# Connectors.net
KiCad netlist of a schematic drawn in Altium Designer
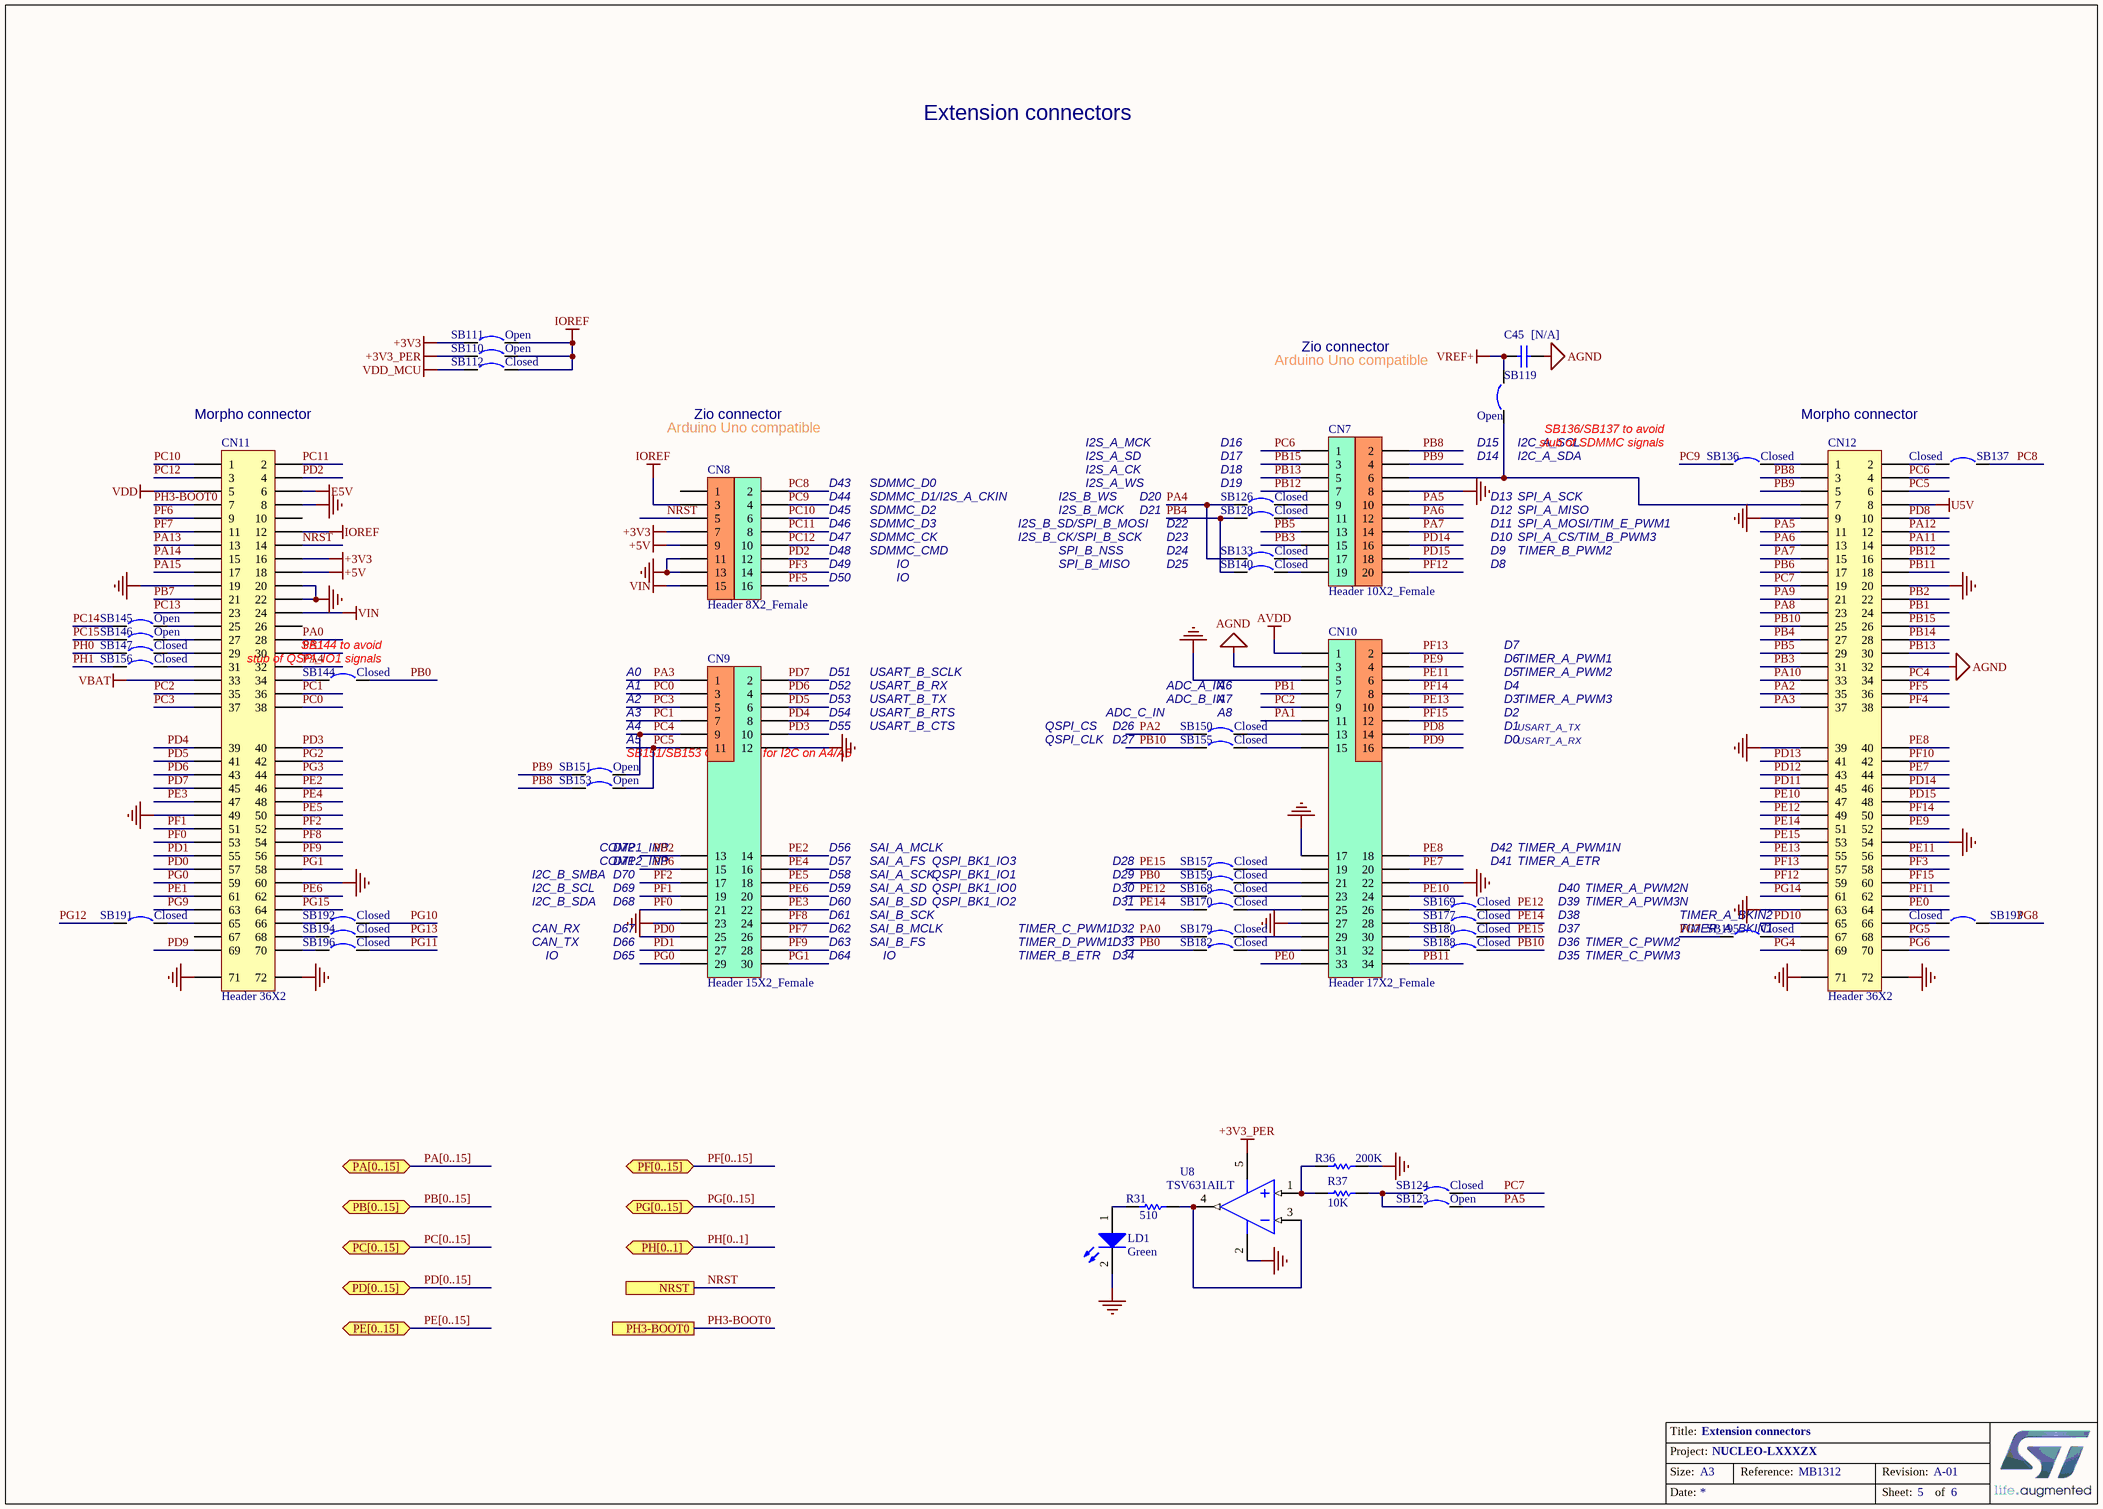
[diagram p0: Connectors.SchDoc]

(export (version "E")
  (design (tool "Eeschema 10.0.6"))
  (components
    (comp (ref "C45")
      (value "[N/A]")
      (footprint "0603C")
      (description "Capacitor,100nF,10%,16V,X7R,0603,YAGEO")
      (fields (field (name "PUBLISHER") "Altium Limited"))
      (libsource (lib "Miscellaneous Devices") (part "Cap"))
    )
    (comp (ref "CN7")
      (value "Header 10X2_Female")
      (footprint "HDR_10x2_2R54_V_F")
      (description "Header, 10-Pin, Dual row,female")
      (fields (field (name "PUBLISHER") "Altium Limited"))
      (libsource (lib "MB1137") (part "Header 10X2_Female"))
    )
    (comp (ref "CN8")
      (value "Header 8X2_Female")
      (footprint "HDR_8x2_2R54_V_F")
      (description "Header, 8-Pin, Dual row,female")
      (fields (field (name "PUBLISHER") "Altium Limited"))
      (libsource (lib "MB1137") (part "Header 8X2_Female"))
    )
    (comp (ref "CN9")
      (value "Header 15X2_Female")
      (footprint "HDR_15x2_2R54_V_F")
      (description "Header, 15-Pin, Dual row,female")
      (fields (field (name "PUBLISHER") "Altium Limited"))
      (libsource (lib "MB1137") (part "Header 15X2_Female"))
    )
    (comp (ref "CN10")
      (value "Header 17X2_Female")
      (footprint "HDR_17x2_2R54_V_F")
      (description "Header, 17-Pin, Dual row,female")
      (fields (field (name "PUBLISHER") "Altium Limited"))
      (libsource (lib "MB1137") (part "Header 17X2_Female"))
    )
    (comp (ref "CN11")
      (value "Header 36X2")
      (footprint "HDR_2x36_2R54_V_M")
      (description "Header, 36-Pin, Dual row")
      (fields (field (name "PUBLISHER") "Altium Limited"))
      (libsource (lib "MB1137") (part "Header 36X2"))
    )
    (comp (ref "CN12")
      (value "Header 36X2")
      (footprint "HDR_2x36_2R54_V_M")
      (description "Header, 36-Pin, Dual row")
      (fields (field (name "PUBLISHER") "Altium Limited"))
      (libsource (lib "MB1137") (part "Header 36X2"))
    )
    (comp (ref "LD1")
      (value "Green")
      (footprint "0603D-G")
      (description "Typical RED, GREEN, YELLOW, AMBER GaAs LED")
      (fields (field (name "PUBLISHER") "Altium Limited"))
      (libsource (lib "Miscellaneous Devices") (part "LED2"))
    )
    (comp (ref "R31")
      (value "510")
      (footprint "0603R")
      (description "Resistor")
      (fields (field (name "PUBLISHER") "Altium Limited"))
      (libsource (lib "Miscellaneous Devices") (part "Res1"))
    )
    (comp (ref "R36")
      (value "200K")
      (footprint "0603R")
      (description "Resistor")
      (fields (field (name "PUBLISHER") "Altium Limited"))
      (libsource (lib "Miscellaneous Devices") (part "res1"))
    )
    (comp (ref "R37")
      (value "10K")
      (footprint "0603R")
      (description "Resistor")
      (fields (field (name "PUBLISHER") "Altium Limited"))
      (libsource (lib "Miscellaneous Devices") (part "res1"))
    )
    (comp (ref "SB110")
      (value "Open")
      (footprint "SB_0603")
      (description "Circuit Breaker")
      (fields (field (name "PUBLISHER") "Altium Limited"))
      (libsource (lib "MB1167") (part "Circuit Breaker"))
    )
    (comp (ref "SB111")
      (value "Open")
      (footprint "SB_0603")
      (description "Circuit Breaker")
      (fields (field (name "PUBLISHER") "Altium Limited"))
      (libsource (lib "MB1167") (part "Circuit Breaker"))
    )
    (comp (ref "SB112")
      (value "Closed")
      (footprint "SB_0603")
      (description "Circuit Breaker")
      (fields (field (name "PUBLISHER") "Altium Limited"))
      (libsource (lib "MB1167") (part "Circuit Breaker_close"))
    )
    (comp (ref "SB119")
      (value "Open")
      (footprint "SB_0603")
      (description "Circuit Breaker")
      (fields (field (name "PUBLISHER") "Altium Limited"))
      (libsource (lib "") (part "Circuit Breaker_2"))
    )
    (comp (ref "SB123")
      (value "Open")
      (footprint "SB_0603")
      (description "Circuit Breaker")
      (fields (field (name "PUBLISHER") "Altium Limited"))
      (libsource (lib "MB1167") (part "Circuit Breaker"))
    )
    (comp (ref "SB124")
      (value "Closed")
      (footprint "SB_0603")
      (description "Circuit Breaker")
      (fields (field (name "PUBLISHER") "Altium Limited"))
      (libsource (lib "") (part "Circuit Breaker_close_1"))
    )
    (comp (ref "SB126")
      (value "Closed")
      (footprint "SB_0603")
      (description "Circuit Breaker")
      (fields (field (name "PUBLISHER") "Altium Limited"))
      (libsource (lib "MB1167") (part "Circuit Breaker_close"))
    )
    (comp (ref "SB128")
      (value "Closed")
      (footprint "SB_0603")
      (description "Circuit Breaker")
      (fields (field (name "PUBLISHER") "Altium Limited"))
      (libsource (lib "MB1167") (part "Circuit Breaker_close"))
    )
    (comp (ref "SB133")
      (value "Closed")
      (footprint "SB_0603")
      (description "Circuit Breaker")
      (fields (field (name "PUBLISHER") "Altium Limited"))
      (libsource (lib "MB1167") (part "Circuit Breaker_close"))
    )
    (comp (ref "SB136")
      (value "Closed")
      (footprint "SB_0603")
      (description "Circuit Breaker")
      (fields (field (name "PUBLISHER") "Altium Limited"))
      (libsource (lib "MB1167") (part "Circuit Breaker_close"))
    )
    (comp (ref "SB137")
      (value "Closed")
      (footprint "SB_0603")
      (description "Circuit Breaker")
      (fields (field (name "PUBLISHER") "Altium Limited"))
      (libsource (lib "") (part "Circuit Breaker_close_1"))
    )
    (comp (ref "SB140")
      (value "Closed")
      (footprint "SB_0603")
      (description "Circuit Breaker")
      (fields (field (name "PUBLISHER") "Altium Limited"))
      (libsource (lib "MB1167") (part "Circuit Breaker_close"))
    )
    (comp (ref "SB144")
      (value "Closed")
      (footprint "SB_0603")
      (description "Circuit Breaker")
      (fields (field (name "PUBLISHER") "Altium Limited"))
      (libsource (lib "MB1167") (part "Circuit Breaker_close"))
    )
    (comp (ref "SB145")
      (value "Open")
      (footprint "SB_0603")
      (description "Circuit Breaker")
      (fields (field (name "PUBLISHER") "Altium Limited"))
      (libsource (lib "MB1167") (part "Circuit Breaker"))
    )
    (comp (ref "SB146")
      (value "Open")
      (footprint "SB_0603")
      (description "Circuit Breaker")
      (fields (field (name "PUBLISHER") "Altium Limited"))
      (libsource (lib "MB1167") (part "Circuit Breaker"))
    )
    (comp (ref "SB147")
      (value "Closed")
      (footprint "SB_0603")
      (description "Circuit Breaker")
      (fields (field (name "PUBLISHER") "Altium Limited"))
      (libsource (lib "MB1167") (part "Circuit Breaker_close"))
    )
    (comp (ref "SB150")
      (value "Closed")
      (footprint "SB_0603")
      (description "Circuit Breaker")
      (fields (field (name "PUBLISHER") "Altium Limited"))
      (libsource (lib "MB1167") (part "Circuit Breaker_close"))
    )
    (comp (ref "SB151")
      (value "Open")
      (footprint "SB_0603")
      (description "Circuit Breaker")
      (fields (field (name "PUBLISHER") "Altium Limited"))
      (libsource (lib "") (part "Circuit Breaker_1"))
    )
    (comp (ref "SB153")
      (value "Open")
      (footprint "SB_0603")
      (description "Circuit Breaker")
      (fields (field (name "PUBLISHER") "Altium Limited"))
      (libsource (lib "") (part "Circuit Breaker_1"))
    )
    (comp (ref "SB155")
      (value "Closed")
      (footprint "SB_0603")
      (description "Circuit Breaker")
      (fields (field (name "PUBLISHER") "Altium Limited"))
      (libsource (lib "MB1167") (part "Circuit Breaker_close"))
    )
    (comp (ref "SB156")
      (value "Closed")
      (footprint "SB_0603")
      (description "Circuit Breaker")
      (fields (field (name "PUBLISHER") "Altium Limited"))
      (libsource (lib "MB1167") (part "Circuit Breaker_close"))
    )
    (comp (ref "SB157")
      (value "Closed")
      (footprint "SB_0603")
      (description "Circuit Breaker")
      (fields (field (name "PUBLISHER") "Altium Limited"))
      (libsource (lib "MB1167") (part "Circuit Breaker_close"))
    )
    (comp (ref "SB159")
      (value "Closed")
      (footprint "SB_0603")
      (description "Circuit Breaker")
      (fields (field (name "PUBLISHER") "Altium Limited"))
      (libsource (lib "MB1167") (part "Circuit Breaker_close"))
    )
    (comp (ref "SB168")
      (value "Closed")
      (footprint "SB_0603")
      (description "Circuit Breaker")
      (fields (field (name "PUBLISHER") "Altium Limited"))
      (libsource (lib "MB1167") (part "Circuit Breaker_close"))
    )
    (comp (ref "SB169")
      (value "Closed")
      (footprint "SB_0603")
      (description "Circuit Breaker")
      (fields (field (name "PUBLISHER") "Altium Limited"))
      (libsource (lib "MB1167") (part "Circuit Breaker_close"))
    )
    (comp (ref "SB170")
      (value "Closed")
      (footprint "SB_0603")
      (description "Circuit Breaker")
      (fields (field (name "PUBLISHER") "Altium Limited"))
      (libsource (lib "MB1167") (part "Circuit Breaker_close"))
    )
    (comp (ref "SB177")
      (value "Closed")
      (footprint "SB_0603")
      (description "Circuit Breaker")
      (fields (field (name "PUBLISHER") "Altium Limited"))
      (libsource (lib "MB1167") (part "Circuit Breaker_close"))
    )
    (comp (ref "SB179")
      (value "Closed")
      (footprint "SB_0603")
      (description "Circuit Breaker")
      (fields (field (name "PUBLISHER") "Altium Limited"))
      (libsource (lib "MB1167") (part "Circuit Breaker_close"))
    )
    (comp (ref "SB180")
      (value "Closed")
      (footprint "SB_0603")
      (description "Circuit Breaker")
      (fields (field (name "PUBLISHER") "Altium Limited"))
      (libsource (lib "MB1167") (part "Circuit Breaker_close"))
    )
    (comp (ref "SB182")
      (value "Closed")
      (footprint "SB_0603")
      (description "Circuit Breaker")
      (fields (field (name "PUBLISHER") "Altium Limited"))
      (libsource (lib "MB1167") (part "Circuit Breaker_close"))
    )
    (comp (ref "SB188")
      (value "Closed")
      (footprint "SB_0603")
      (description "Circuit Breaker")
      (fields (field (name "PUBLISHER") "Altium Limited"))
      (libsource (lib "MB1167") (part "Circuit Breaker_close"))
    )
    (comp (ref "SB191")
      (value "Closed")
      (footprint "SB_0603")
      (description "Circuit Breaker")
      (fields (field (name "PUBLISHER") "Altium Limited"))
      (libsource (lib "MB1167") (part "Circuit Breaker_close"))
    )
    (comp (ref "SB192")
      (value "Closed")
      (footprint "SB_0603")
      (description "Circuit Breaker")
      (fields (field (name "PUBLISHER") "Altium Limited"))
      (libsource (lib "MB1167") (part "Circuit Breaker_close"))
    )
    (comp (ref "SB193")
      (value "Closed")
      (footprint "SB_0603")
      (description "Circuit Breaker")
      (fields (field (name "PUBLISHER") "Altium Limited"))
      (libsource (lib "MB1167") (part "Circuit Breaker_close"))
    )
    (comp (ref "SB194")
      (value "Closed")
      (footprint "SB_0603")
      (description "Circuit Breaker")
      (fields (field (name "PUBLISHER") "Altium Limited"))
      (libsource (lib "MB1167") (part "Circuit Breaker_close"))
    )
    (comp (ref "SB195")
      (value "Closed")
      (footprint "SB_0603")
      (description "Circuit Breaker")
      (fields (field (name "PUBLISHER") "Altium Limited"))
      (libsource (lib "MB1167") (part "Circuit Breaker_close"))
    )
    (comp (ref "SB196")
      (value "Closed")
      (footprint "SB_0603")
      (description "Circuit Breaker")
      (fields (field (name "PUBLISHER") "Altium Limited"))
      (libsource (lib "MB1167") (part "Circuit Breaker_close"))
    )
    (comp (ref "U8")
      (value "TSV631AILT")
      (footprint "SOT-23-5L")
      (libsource (lib "MB988") (part "TSV631AILT"))
    )
  )
  (nets
    (net (code "1") (name "+3V3") (class "Default")
      (node (ref "CN11") (pin "16") (pinfunction "16_16") (pintype "passive"))
      (node (ref "CN8") (pin "7") (pinfunction "7_7") (pintype "passive"))
      (node (ref "SB111") (pin "1") (pinfunction "1_1") (pintype "passive"))
    )
    (net (code "2") (name "+3V3_PER") (class "Default")
      (node (ref "SB110") (pin "1") (pinfunction "1_1") (pintype "passive"))
      (node (ref "U8") (pin "5") (pinfunction "VCC_5") (pintype "power_in"))
    )
    (net (code "3") (name "+5V") (class "Default")
      (node (ref "CN11") (pin "18") (pinfunction "18_18") (pintype "passive"))
      (node (ref "CN8") (pin "9") (pinfunction "9_9") (pintype "passive"))
    )
    (net (code "4") (name "/NRST") (class "Default")
      (node (ref "CN11") (pin "14") (pinfunction "14_14") (pintype "passive"))
      (node (ref "CN8") (pin "5") (pinfunction "5_5") (pintype "passive"))
    )
    (net (code "5") (name "/PA0") (class "Default")
      (node (ref "CN11") (pin "28") (pinfunction "28_28") (pintype "passive"))
      (node (ref "SB179") (pin "1") (pinfunction "1_1") (pintype "passive"))
    )
    (net (code "6") (name "/PA1") (class "Default")
      (node (ref "CN10") (pin "11") (pinfunction "11_11") (pintype "passive"))
      (node (ref "CN11") (pin "30") (pinfunction "30_30") (pintype "passive"))
    )
    (net (code "7") (name "/PA2") (class "Default")
      (node (ref "CN12") (pin "35") (pinfunction "35_35") (pintype "passive"))
      (node (ref "SB150") (pin "1") (pinfunction "1_1") (pintype "passive"))
    )
    (net (code "8") (name "/PA3") (class "Default")
      (node (ref "CN12") (pin "37") (pinfunction "37_37") (pintype "passive"))
      (node (ref "CN9") (pin "1") (pinfunction "1_1") (pintype "passive"))
    )
    (net (code "9") (name "/PA4") (class "Default")
      (node (ref "CN11") (pin "32") (pinfunction "32_32") (pintype "passive"))
      (node (ref "SB126") (pin "1") (pinfunction "1_1") (pintype "passive"))
      (node (ref "SB133") (pin "1") (pinfunction "1_1") (pintype "passive"))
    )
    (net (code "10") (name "/PA5") (class "Default")
      (node (ref "CN12") (pin "11") (pinfunction "11_11") (pintype "passive"))
      (node (ref "CN7") (pin "10") (pinfunction "10_10") (pintype "passive"))
      (node (ref "SB123") (pin "2") (pinfunction "2_2") (pintype "passive"))
    )
    (net (code "11") (name "/PA6") (class "Default")
      (node (ref "CN12") (pin "13") (pinfunction "13_13") (pintype "passive"))
      (node (ref "CN7") (pin "12") (pinfunction "12_12") (pintype "passive"))
    )
    (net (code "12") (name "/PA7") (class "Default")
      (node (ref "CN12") (pin "15") (pinfunction "15_15") (pintype "passive"))
      (node (ref "CN7") (pin "14") (pinfunction "14_14") (pintype "passive"))
    )
    (net (code "13") (name "/PA8") (class "Default")
      (node (ref "CN12") (pin "23") (pinfunction "23_23") (pintype "passive"))
    )
    (net (code "14") (name "/PA9") (class "Default")
      (node (ref "CN12") (pin "21") (pinfunction "21_21") (pintype "passive"))
    )
    (net (code "15") (name "/PA10") (class "Default")
      (node (ref "CN12") (pin "33") (pinfunction "33_33") (pintype "passive"))
    )
    (net (code "16") (name "/PA11") (class "Default")
      (node (ref "CN12") (pin "14") (pinfunction "14_14") (pintype "passive"))
    )
    (net (code "17") (name "/PA12") (class "Default")
      (node (ref "CN12") (pin "12") (pinfunction "12_12") (pintype "passive"))
    )
    (net (code "18") (name "/PA13") (class "Default")
      (node (ref "CN11") (pin "13") (pinfunction "13_13") (pintype "passive"))
    )
    (net (code "19") (name "/PA14") (class "Default")
      (node (ref "CN11") (pin "15") (pinfunction "15_15") (pintype "passive"))
    )
    (net (code "20") (name "/PA15") (class "Default")
      (node (ref "CN11") (pin "17") (pinfunction "17_17") (pintype "passive"))
    )
    (net (code "22") (name "/PB0") (class "Default")
      (node (ref "SB144") (pin "2") (pinfunction "2_2") (pintype "passive"))
      (node (ref "SB159") (pin "1") (pinfunction "1_1") (pintype "passive"))
      (node (ref "SB182") (pin "1") (pinfunction "1_1") (pintype "passive"))
    )
    (net (code "23") (name "/PB1") (class "Default")
      (node (ref "CN10") (pin "7") (pinfunction "7_7") (pintype "passive"))
      (node (ref "CN12") (pin "24") (pinfunction "24_24") (pintype "passive"))
    )
    (net (code "24") (name "/PB2") (class "Default")
      (node (ref "CN12") (pin "22") (pinfunction "22_22") (pintype "passive"))
      (node (ref "CN9") (pin "13") (pinfunction "13_13") (pintype "passive"))
    )
    (net (code "25") (name "/PB3") (class "Default")
      (node (ref "CN12") (pin "31") (pinfunction "31_31") (pintype "passive"))
      (node (ref "CN7") (pin "15") (pinfunction "15_15") (pintype "passive"))
    )
    (net (code "26") (name "/PB4") (class "Default")
      (node (ref "CN12") (pin "27") (pinfunction "27_27") (pintype "passive"))
      (node (ref "SB128") (pin "1") (pinfunction "1_1") (pintype "passive"))
      (node (ref "SB140") (pin "1") (pinfunction "1_1") (pintype "passive"))
    )
    (net (code "27") (name "/PB5") (class "Default")
      (node (ref "CN12") (pin "29") (pinfunction "29_29") (pintype "passive"))
      (node (ref "CN7") (pin "13") (pinfunction "13_13") (pintype "passive"))
    )
    (net (code "28") (name "/PB6") (class "Default")
      (node (ref "CN12") (pin "17") (pinfunction "17_17") (pintype "passive"))
      (node (ref "CN9") (pin "15") (pinfunction "15_15") (pintype "passive"))
    )
    (net (code "29") (name "/PB7") (class "Default")
      (node (ref "CN11") (pin "21") (pinfunction "21_21") (pintype "passive"))
    )
    (net (code "30") (name "/PB8") (class "Default")
      (node (ref "CN12") (pin "3") (pinfunction "3_3") (pintype "passive"))
      (node (ref "CN7") (pin "2") (pinfunction "2_2") (pintype "passive"))
      (node (ref "SB153") (pin "2") (pinfunction "2_2") (pintype "passive"))
    )
    (net (code "31") (name "/PB9") (class "Default")
      (node (ref "CN12") (pin "5") (pinfunction "5_5") (pintype "passive"))
      (node (ref "CN7") (pin "4") (pinfunction "4_4") (pintype "passive"))
      (node (ref "SB151") (pin "2") (pinfunction "2_2") (pintype "passive"))
    )
    (net (code "32") (name "/PB10") (class "Default")
      (node (ref "CN12") (pin "25") (pinfunction "25_25") (pintype "passive"))
      (node (ref "SB155") (pin "1") (pinfunction "1_1") (pintype "passive"))
      (node (ref "SB188") (pin "2") (pinfunction "2_2") (pintype "passive"))
    )
    (net (code "33") (name "/PB11") (class "Default")
      (node (ref "CN10") (pin "34") (pinfunction "34_34") (pintype "passive"))
      (node (ref "CN12") (pin "18") (pinfunction "18_18") (pintype "passive"))
    )
    (net (code "34") (name "/PB12") (class "Default")
      (node (ref "CN12") (pin "16") (pinfunction "16_16") (pintype "passive"))
      (node (ref "CN7") (pin "7") (pinfunction "7_7") (pintype "passive"))
    )
    (net (code "35") (name "/PB13") (class "Default")
      (node (ref "CN12") (pin "30") (pinfunction "30_30") (pintype "passive"))
      (node (ref "CN7") (pin "5") (pinfunction "5_5") (pintype "passive"))
    )
    (net (code "36") (name "/PB14") (class "Default")
      (node (ref "CN12") (pin "28") (pinfunction "28_28") (pintype "passive"))
    )
    (net (code "37") (name "/PB15") (class "Default")
      (node (ref "CN12") (pin "26") (pinfunction "26_26") (pintype "passive"))
      (node (ref "CN7") (pin "3") (pinfunction "3_3") (pintype "passive"))
    )
    (net (code "39") (name "/PC0") (class "Default")
      (node (ref "CN11") (pin "38") (pinfunction "38_38") (pintype "passive"))
      (node (ref "CN9") (pin "3") (pinfunction "3_3") (pintype "passive"))
    )
    (net (code "40") (name "/PC1") (class "Default")
      (node (ref "CN11") (pin "36") (pinfunction "36_36") (pintype "passive"))
      (node (ref "CN9") (pin "7") (pinfunction "7_7") (pintype "passive"))
    )
    (net (code "41") (name "/PC2") (class "Default")
      (node (ref "CN10") (pin "9") (pinfunction "9_9") (pintype "passive"))
      (node (ref "CN11") (pin "35") (pinfunction "35_35") (pintype "passive"))
    )
    (net (code "42") (name "/PC3") (class "Default")
      (node (ref "CN11") (pin "37") (pinfunction "37_37") (pintype "passive"))
      (node (ref "CN9") (pin "5") (pinfunction "5_5") (pintype "passive"))
    )
    (net (code "43") (name "/PC4") (class "Default")
      (node (ref "CN12") (pin "34") (pinfunction "34_34") (pintype "passive"))
      (node (ref "CN9") (pin "9") (pinfunction "9_9") (pintype "passive"))
      (node (ref "SB151") (pin "1") (pinfunction "1_1") (pintype "passive"))
    )
    (net (code "44") (name "/PC5") (class "Default")
      (node (ref "CN12") (pin "6") (pinfunction "6_6") (pintype "passive"))
      (node (ref "CN9") (pin "11") (pinfunction "11_11") (pintype "passive"))
      (node (ref "SB153") (pin "1") (pinfunction "1_1") (pintype "passive"))
    )
    (net (code "45") (name "/PC6") (class "Default")
      (node (ref "CN12") (pin "4") (pinfunction "4_4") (pintype "passive"))
      (node (ref "CN7") (pin "1") (pinfunction "1_1") (pintype "passive"))
    )
    (net (code "46") (name "/PC7") (class "Default")
      (node (ref "CN12") (pin "19") (pinfunction "19_19") (pintype "passive"))
      (node (ref "SB124") (pin "1") (pinfunction "1_1") (pintype "passive"))
    )
    (net (code "47") (name "/PC8") (class "Default")
      (node (ref "CN8") (pin "2") (pinfunction "2_2") (pintype "passive"))
      (node (ref "SB137") (pin "1") (pinfunction "1_1") (pintype "passive"))
    )
    (net (code "48") (name "/PC9") (class "Default")
      (node (ref "CN8") (pin "4") (pinfunction "4_4") (pintype "passive"))
      (node (ref "SB136") (pin "1") (pinfunction "1_1") (pintype "passive"))
    )
    (net (code "49") (name "/PC10") (class "Default")
      (node (ref "CN11") (pin "1") (pinfunction "1_1") (pintype "passive"))
      (node (ref "CN8") (pin "6") (pinfunction "6_6") (pintype "passive"))
    )
    (net (code "50") (name "/PC11") (class "Default")
      (node (ref "CN11") (pin "2") (pinfunction "2_2") (pintype "passive"))
      (node (ref "CN8") (pin "8") (pinfunction "8_8") (pintype "passive"))
    )
    (net (code "51") (name "/PC12") (class "Default")
      (node (ref "CN11") (pin "3") (pinfunction "3_3") (pintype "passive"))
      (node (ref "CN8") (pin "10") (pinfunction "10_10") (pintype "passive"))
    )
    (net (code "52") (name "/PC13") (class "Default")
      (node (ref "CN11") (pin "23") (pinfunction "23_23") (pintype "passive"))
    )
    (net (code "53") (name "/PC14") (class "Default")
      (node (ref "SB145") (pin "1") (pinfunction "1_1") (pintype "passive"))
    )
    (net (code "54") (name "/PC15") (class "Default")
      (node (ref "SB146") (pin "1") (pinfunction "1_1") (pintype "passive"))
    )
    (net (code "56") (name "/PD0") (class "Default")
      (node (ref "CN11") (pin "57") (pinfunction "57_57") (pintype "passive"))
      (node (ref "CN9") (pin "25") (pinfunction "25_25") (pintype "passive"))
    )
    (net (code "57") (name "/PD1") (class "Default")
      (node (ref "CN11") (pin "55") (pinfunction "55_55") (pintype "passive"))
      (node (ref "CN9") (pin "27") (pinfunction "27_27") (pintype "passive"))
    )
    (net (code "58") (name "/PD2") (class "Default")
      (node (ref "CN11") (pin "4") (pinfunction "4_4") (pintype "passive"))
      (node (ref "CN8") (pin "12") (pinfunction "12_12") (pintype "passive"))
    )
    (net (code "59") (name "/PD3") (class "Default")
      (node (ref "CN11") (pin "40") (pinfunction "40_40") (pintype "passive"))
      (node (ref "CN9") (pin "10") (pinfunction "10_10") (pintype "passive"))
    )
    (net (code "60") (name "/PD4") (class "Default")
      (node (ref "CN11") (pin "39") (pinfunction "39_39") (pintype "passive"))
      (node (ref "CN9") (pin "8") (pinfunction "8_8") (pintype "passive"))
    )
    (net (code "61") (name "/PD5") (class "Default")
      (node (ref "CN11") (pin "41") (pinfunction "41_41") (pintype "passive"))
      (node (ref "CN9") (pin "6") (pinfunction "6_6") (pintype "passive"))
    )
    (net (code "62") (name "/PD6") (class "Default")
      (node (ref "CN11") (pin "43") (pinfunction "43_43") (pintype "passive"))
      (node (ref "CN9") (pin "4") (pinfunction "4_4") (pintype "passive"))
    )
    (net (code "63") (name "/PD7") (class "Default")
      (node (ref "CN11") (pin "45") (pinfunction "45_45") (pintype "passive"))
      (node (ref "CN9") (pin "2") (pinfunction "2_2") (pintype "passive"))
    )
    (net (code "64") (name "/PD8") (class "Default")
      (node (ref "CN10") (pin "14") (pinfunction "14_14") (pintype "passive"))
      (node (ref "CN12") (pin "10") (pinfunction "10_10") (pintype "passive"))
    )
    (net (code "65") (name "/PD9") (class "Default")
      (node (ref "CN10") (pin "16") (pinfunction "16_16") (pintype "passive"))
      (node (ref "CN11") (pin "69") (pinfunction "69_69") (pintype "passive"))
    )
    (net (code "66") (name "/PD10") (class "Default")
      (node (ref "CN12") (pin "65") (pinfunction "65_65") (pintype "passive"))
    )
    (net (code "67") (name "/PD11") (class "Default")
      (node (ref "CN12") (pin "45") (pinfunction "45_45") (pintype "passive"))
    )
    (net (code "68") (name "/PD12") (class "Default")
      (node (ref "CN12") (pin "43") (pinfunction "43_43") (pintype "passive"))
    )
    (net (code "69") (name "/PD13") (class "Default")
      (node (ref "CN12") (pin "41") (pinfunction "41_41") (pintype "passive"))
    )
    (net (code "70") (name "/PD14") (class "Default")
      (node (ref "CN12") (pin "46") (pinfunction "46_46") (pintype "passive"))
      (node (ref "CN7") (pin "16") (pinfunction "16_16") (pintype "passive"))
    )
    (net (code "71") (name "/PD15") (class "Default")
      (node (ref "CN12") (pin "48") (pinfunction "48_48") (pintype "passive"))
      (node (ref "CN7") (pin "18") (pinfunction "18_18") (pintype "passive"))
    )
    (net (code "73") (name "/PE0") (class "Default")
      (node (ref "CN10") (pin "33") (pinfunction "33_33") (pintype "passive"))
      (node (ref "CN12") (pin "64") (pinfunction "64_64") (pintype "passive"))
    )
    (net (code "74") (name "/PE1") (class "Default")
      (node (ref "CN11") (pin "61") (pinfunction "61_61") (pintype "passive"))
    )
    (net (code "75") (name "/PE2") (class "Default")
      (node (ref "CN11") (pin "46") (pinfunction "46_46") (pintype "passive"))
      (node (ref "CN9") (pin "14") (pinfunction "14_14") (pintype "passive"))
    )
    (net (code "76") (name "/PE3") (class "Default")
      (node (ref "CN11") (pin "47") (pinfunction "47_47") (pintype "passive"))
      (node (ref "CN9") (pin "22") (pinfunction "22_22") (pintype "passive"))
    )
    (net (code "77") (name "/PE4") (class "Default")
      (node (ref "CN11") (pin "48") (pinfunction "48_48") (pintype "passive"))
      (node (ref "CN9") (pin "16") (pinfunction "16_16") (pintype "passive"))
    )
    (net (code "78") (name "/PE5") (class "Default")
      (node (ref "CN11") (pin "50") (pinfunction "50_50") (pintype "passive"))
      (node (ref "CN9") (pin "18") (pinfunction "18_18") (pintype "passive"))
    )
    (net (code "79") (name "/PE6") (class "Default")
      (node (ref "CN11") (pin "62") (pinfunction "62_62") (pintype "passive"))
      (node (ref "CN9") (pin "20") (pinfunction "20_20") (pintype "passive"))
    )
    (net (code "80") (name "/PE7") (class "Default")
      (node (ref "CN10") (pin "20") (pinfunction "20_20") (pintype "passive"))
      (node (ref "CN12") (pin "44") (pinfunction "44_44") (pintype "passive"))
    )
    (net (code "81") (name "/PE8") (class "Default")
      (node (ref "CN10") (pin "18") (pinfunction "18_18") (pintype "passive"))
      (node (ref "CN12") (pin "40") (pinfunction "40_40") (pintype "passive"))
    )
    (net (code "82") (name "/PE9") (class "Default")
      (node (ref "CN10") (pin "4") (pinfunction "4_4") (pintype "passive"))
      (node (ref "CN12") (pin "52") (pinfunction "52_52") (pintype "passive"))
    )
    (net (code "83") (name "/PE10") (class "Default")
      (node (ref "CN10") (pin "24") (pinfunction "24_24") (pintype "passive"))
      (node (ref "CN12") (pin "47") (pinfunction "47_47") (pintype "passive"))
    )
    (net (code "84") (name "/PE11") (class "Default")
      (node (ref "CN10") (pin "6") (pinfunction "6_6") (pintype "passive"))
      (node (ref "CN12") (pin "56") (pinfunction "56_56") (pintype "passive"))
    )
    (net (code "85") (name "/PE12") (class "Default")
      (node (ref "CN12") (pin "49") (pinfunction "49_49") (pintype "passive"))
      (node (ref "SB168") (pin "1") (pinfunction "1_1") (pintype "passive"))
      (node (ref "SB169") (pin "2") (pinfunction "2_2") (pintype "passive"))
    )
    (net (code "86") (name "/PE13") (class "Default")
      (node (ref "CN10") (pin "10") (pinfunction "10_10") (pintype "passive"))
      (node (ref "CN12") (pin "55") (pinfunction "55_55") (pintype "passive"))
    )
    (net (code "87") (name "/PE14") (class "Default")
      (node (ref "CN12") (pin "51") (pinfunction "51_51") (pintype "passive"))
      (node (ref "SB170") (pin "1") (pinfunction "1_1") (pintype "passive"))
      (node (ref "SB177") (pin "2") (pinfunction "2_2") (pintype "passive"))
    )
    (net (code "88") (name "/PE15") (class "Default")
      (node (ref "CN12") (pin "53") (pinfunction "53_53") (pintype "passive"))
      (node (ref "SB157") (pin "1") (pinfunction "1_1") (pintype "passive"))
      (node (ref "SB180") (pin "2") (pinfunction "2_2") (pintype "passive"))
    )
    (net (code "90") (name "/PF0") (class "Default")
      (node (ref "CN11") (pin "53") (pinfunction "53_53") (pintype "passive"))
      (node (ref "CN9") (pin "21") (pinfunction "21_21") (pintype "passive"))
    )
    (net (code "91") (name "/PF1") (class "Default")
      (node (ref "CN11") (pin "51") (pinfunction "51_51") (pintype "passive"))
      (node (ref "CN9") (pin "19") (pinfunction "19_19") (pintype "passive"))
    )
    (net (code "92") (name "/PF2") (class "Default")
      (node (ref "CN11") (pin "52") (pinfunction "52_52") (pintype "passive"))
      (node (ref "CN9") (pin "17") (pinfunction "17_17") (pintype "passive"))
    )
    (net (code "93") (name "/PF3") (class "Default")
      (node (ref "CN12") (pin "58") (pinfunction "58_58") (pintype "passive"))
      (node (ref "CN8") (pin "14") (pinfunction "14_14") (pintype "passive"))
    )
    (net (code "94") (name "/PF4") (class "Default")
      (node (ref "CN12") (pin "38") (pinfunction "38_38") (pintype "passive"))
    )
    (net (code "95") (name "/PF5") (class "Default")
      (node (ref "CN12") (pin "36") (pinfunction "36_36") (pintype "passive"))
      (node (ref "CN8") (pin "16") (pinfunction "16_16") (pintype "passive"))
    )
    (net (code "96") (name "/PF6") (class "Default")
      (node (ref "CN11") (pin "9") (pinfunction "9_9") (pintype "passive"))
    )
    (net (code "97") (name "/PF7") (class "Default")
      (node (ref "CN11") (pin "11") (pinfunction "11_11") (pintype "passive"))
      (node (ref "CN9") (pin "26") (pinfunction "26_26") (pintype "passive"))
    )
    (net (code "98") (name "/PF8") (class "Default")
      (node (ref "CN11") (pin "54") (pinfunction "54_54") (pintype "passive"))
      (node (ref "CN9") (pin "24") (pinfunction "24_24") (pintype "passive"))
    )
    (net (code "99") (name "/PF9") (class "Default")
      (node (ref "CN11") (pin "56") (pinfunction "56_56") (pintype "passive"))
      (node (ref "CN9") (pin "28") (pinfunction "28_28") (pintype "passive"))
    )
    (net (code "100") (name "/PF10") (class "Default")
      (node (ref "CN12") (pin "42") (pinfunction "42_42") (pintype "passive"))
    )
    (net (code "101") (name "/PF11") (class "Default")
      (node (ref "CN12") (pin "62") (pinfunction "62_62") (pintype "passive"))
    )
    (net (code "102") (name "/PF12") (class "Default")
      (node (ref "CN12") (pin "59") (pinfunction "59_59") (pintype "passive"))
      (node (ref "CN7") (pin "20") (pinfunction "20_20") (pintype "passive"))
    )
    (net (code "103") (name "/PF13") (class "Default")
      (node (ref "CN10") (pin "2") (pinfunction "2_2") (pintype "passive"))
      (node (ref "CN12") (pin "57") (pinfunction "57_57") (pintype "passive"))
    )
    (net (code "104") (name "/PF14") (class "Default")
      (node (ref "CN10") (pin "8") (pinfunction "8_8") (pintype "passive"))
      (node (ref "CN12") (pin "50") (pinfunction "50_50") (pintype "passive"))
    )
    (net (code "105") (name "/PF15") (class "Default")
      (node (ref "CN10") (pin "12") (pinfunction "12_12") (pintype "passive"))
      (node (ref "CN12") (pin "60") (pinfunction "60_60") (pintype "passive"))
    )
    (net (code "107") (name "/PG0") (class "Default")
      (node (ref "CN11") (pin "59") (pinfunction "59_59") (pintype "passive"))
      (node (ref "CN9") (pin "29") (pinfunction "29_29") (pintype "passive"))
    )
    (net (code "108") (name "/PG1") (class "Default")
      (node (ref "CN11") (pin "58") (pinfunction "58_58") (pintype "passive"))
      (node (ref "CN9") (pin "30") (pinfunction "30_30") (pintype "passive"))
    )
    (net (code "109") (name "/PG2") (class "Default")
      (node (ref "CN11") (pin "42") (pinfunction "42_42") (pintype "passive"))
    )
    (net (code "110") (name "/PG3") (class "Default")
      (node (ref "CN11") (pin "44") (pinfunction "44_44") (pintype "passive"))
    )
    (net (code "111") (name "/PG4") (class "Default")
      (node (ref "CN12") (pin "69") (pinfunction "69_69") (pintype "passive"))
    )
    (net (code "112") (name "/PG5") (class "Default")
      (node (ref "CN12") (pin "68") (pinfunction "68_68") (pintype "passive"))
    )
    (net (code "113") (name "/PG6") (class "Default")
      (node (ref "CN12") (pin "70") (pinfunction "70_70") (pintype "passive"))
    )
    (net (code "114") (name "/PG7") (class "Default")
      (node (ref "SB195") (pin "1") (pinfunction "1_1") (pintype "passive"))
    )
    (net (code "115") (name "/PG8") (class "Default")
      (node (ref "SB193") (pin "2") (pinfunction "2_2") (pintype "passive"))
    )
    (net (code "116") (name "/PG9") (class "Default")
      (node (ref "CN11") (pin "63") (pinfunction "63_63") (pintype "passive"))
    )
    (net (code "117") (name "/PG10") (class "Default")
      (node (ref "SB192") (pin "2") (pinfunction "2_2") (pintype "passive"))
    )
    (net (code "118") (name "/PG11") (class "Default")
      (node (ref "SB196") (pin "2") (pinfunction "2_2") (pintype "passive"))
    )
    (net (code "119") (name "/PG12") (class "Default")
      (node (ref "SB191") (pin "1") (pinfunction "1_1") (pintype "passive"))
    )
    (net (code "120") (name "/PG13") (class "Default")
      (node (ref "SB194") (pin "2") (pinfunction "2_2") (pintype "passive"))
    )
    (net (code "121") (name "/PG14") (class "Default")
      (node (ref "CN12") (pin "61") (pinfunction "61_61") (pintype "passive"))
    )
    (net (code "122") (name "/PG15") (class "Default")
      (node (ref "CN11") (pin "64") (pinfunction "64_64") (pintype "passive"))
    )
    (net (code "124") (name "/PH0") (class "Default")
      (node (ref "SB147") (pin "1") (pinfunction "1_1") (pintype "passive"))
    )
    (net (code "125") (name "/PH1") (class "Default")
      (node (ref "SB156") (pin "1") (pinfunction "1_1") (pintype "passive"))
    )
    (net (code "126") (name "/PH3-BOOT0") (class "Default")
      (node (ref "CN11") (pin "7") (pinfunction "7_7") (pintype "passive"))
    )
    (net (code "128") (name "AGND") (class "Default")
      (node (ref "C45") (pin "2") (pinfunction "2_2") (pintype "passive"))
      (node (ref "CN10") (pin "3") (pinfunction "3_3") (pintype "passive"))
      (node (ref "CN12") (pin "32") (pinfunction "32_32") (pintype "passive"))
    )
    (net (code "129") (name "AVDD") (class "Default")
      (node (ref "CN10") (pin "1") (pinfunction "1_1") (pintype "passive"))
    )
    (net (code "130") (name "E5V") (class "Default")
      (node (ref "CN11") (pin "6") (pinfunction "6_6") (pintype "passive"))
    )
    (net (code "131") (name "GND") (class "Default")
      (node (ref "CN10") (pin "17") (pinfunction "17_17") (pintype "passive"))
      (node (ref "CN10") (pin "22") (pinfunction "22_22") (pintype "passive"))
      (node (ref "CN10") (pin "27") (pinfunction "27_27") (pintype "passive"))
      (node (ref "CN10") (pin "5") (pinfunction "5_5") (pintype "passive"))
      (node (ref "CN11") (pin "19") (pinfunction "19_19") (pintype "passive"))
      (node (ref "CN11") (pin "20") (pinfunction "20_20") (pintype "passive"))
      (node (ref "CN11") (pin "22") (pinfunction "22_22") (pintype "passive"))
      (node (ref "CN11") (pin "49") (pinfunction "49_49") (pintype "passive"))
      (node (ref "CN11") (pin "60") (pinfunction "60_60") (pintype "passive"))
      (node (ref "CN11") (pin "71") (pinfunction "71_71") (pintype "passive"))
      (node (ref "CN11") (pin "72") (pinfunction "72_72") (pintype "passive"))
      (node (ref "CN11") (pin "8") (pinfunction "8_8") (pintype "passive"))
      (node (ref "CN12") (pin "20") (pinfunction "20_20") (pintype "passive"))
      (node (ref "CN12") (pin "39") (pinfunction "39_39") (pintype "passive"))
      (node (ref "CN12") (pin "54") (pinfunction "54_54") (pintype "passive"))
      (node (ref "CN12") (pin "63") (pinfunction "63_63") (pintype "passive"))
      (node (ref "CN12") (pin "71") (pinfunction "71_71") (pintype "passive"))
      (node (ref "CN12") (pin "72") (pinfunction "72_72") (pintype "passive"))
      (node (ref "CN12") (pin "9") (pinfunction "9_9") (pintype "passive"))
      (node (ref "CN7") (pin "8") (pinfunction "8_8") (pintype "passive"))
      (node (ref "CN8") (pin "11") (pinfunction "11_11") (pintype "passive"))
      (node (ref "CN8") (pin "13") (pinfunction "13_13") (pintype "passive"))
      (node (ref "CN9") (pin "12") (pinfunction "12_12") (pintype "passive"))
      (node (ref "CN9") (pin "23") (pinfunction "23_23") (pintype "passive"))
      (node (ref "LD1") (pin "2") (pinfunction "K_2") (pintype "passive"))
      (node (ref "R36") (pin "2") (pinfunction "2_2") (pintype "passive"))
      (node (ref "U8") (pin "2") (pinfunction "VDD_2") (pintype "power_in"))
    )
    (net (code "132") (name "IOREF") (class "Default")
      (node (ref "CN11") (pin "12") (pinfunction "12_12") (pintype "passive"))
      (node (ref "CN8") (pin "3") (pinfunction "3_3") (pintype "passive"))
      (node (ref "SB110") (pin "2") (pinfunction "2_2") (pintype "passive"))
      (node (ref "SB111") (pin "2") (pinfunction "2_2") (pintype "passive"))
      (node (ref "SB112") (pin "2") (pinfunction "2_2") (pintype "passive"))
    )
    (net (code "133") (name "Net-(CN7-Pad9)") (class "Default")
      (node (ref "CN7") (pin "9") (pinfunction "9_9") (pintype "passive"))
      (node (ref "SB126") (pin "2") (pinfunction "2_2") (pintype "passive"))
    )
    (net (code "134") (name "Net-(CN7-Pad11)") (class "Default")
      (node (ref "CN7") (pin "11") (pinfunction "11_11") (pintype "passive"))
      (node (ref "SB128") (pin "2") (pinfunction "2_2") (pintype "passive"))
    )
    (net (code "135") (name "Net-(CN7-Pad17)") (class "Default")
      (node (ref "CN7") (pin "17") (pinfunction "17_17") (pintype "passive"))
      (node (ref "SB133") (pin "2") (pinfunction "2_2") (pintype "passive"))
    )
    (net (code "136") (name "Net-(CN7-Pad19)") (class "Default")
      (node (ref "CN7") (pin "19") (pinfunction "19_19") (pintype "passive"))
      (node (ref "SB140") (pin "2") (pinfunction "2_2") (pintype "passive"))
    )
    (net (code "137") (name "Net-(CN10-Pad13)") (class "Default")
      (node (ref "CN10") (pin "13") (pinfunction "13_13") (pintype "passive"))
      (node (ref "SB150") (pin "2") (pinfunction "2_2") (pintype "passive"))
    )
    (net (code "138") (name "Net-(CN10-Pad15)") (class "Default")
      (node (ref "CN10") (pin "15") (pinfunction "15_15") (pintype "passive"))
      (node (ref "SB155") (pin "2") (pinfunction "2_2") (pintype "passive"))
    )
    (net (code "139") (name "Net-(CN10-Pad19)") (class "Default")
      (node (ref "CN10") (pin "19") (pinfunction "19_19") (pintype "passive"))
      (node (ref "SB157") (pin "2") (pinfunction "2_2") (pintype "passive"))
    )
    (net (code "140") (name "Net-(CN10-Pad21)") (class "Default")
      (node (ref "CN10") (pin "21") (pinfunction "21_21") (pintype "passive"))
      (node (ref "SB159") (pin "2") (pinfunction "2_2") (pintype "passive"))
    )
    (net (code "141") (name "Net-(CN10-Pad23)") (class "Default")
      (node (ref "CN10") (pin "23") (pinfunction "23_23") (pintype "passive"))
      (node (ref "SB168") (pin "2") (pinfunction "2_2") (pintype "passive"))
    )
    (net (code "142") (name "Net-(CN10-Pad25)") (class "Default")
      (node (ref "CN10") (pin "25") (pinfunction "25_25") (pintype "passive"))
      (node (ref "SB170") (pin "2") (pinfunction "2_2") (pintype "passive"))
    )
    (net (code "143") (name "Net-(CN10-Pad26)") (class "Default")
      (node (ref "CN10") (pin "26") (pinfunction "26_26") (pintype "passive"))
      (node (ref "SB169") (pin "1") (pinfunction "1_1") (pintype "passive"))
    )
    (net (code "144") (name "Net-(CN10-Pad28)") (class "Default")
      (node (ref "CN10") (pin "28") (pinfunction "28_28") (pintype "passive"))
      (node (ref "SB177") (pin "1") (pinfunction "1_1") (pintype "passive"))
    )
    (net (code "145") (name "Net-(CN10-Pad29)") (class "Default")
      (node (ref "CN10") (pin "29") (pinfunction "29_29") (pintype "passive"))
      (node (ref "SB179") (pin "2") (pinfunction "2_2") (pintype "passive"))
    )
    (net (code "146") (name "Net-(CN10-Pad30)") (class "Default")
      (node (ref "CN10") (pin "30") (pinfunction "30_30") (pintype "passive"))
      (node (ref "SB180") (pin "1") (pinfunction "1_1") (pintype "passive"))
    )
    (net (code "147") (name "Net-(CN10-Pad31)") (class "Default")
      (node (ref "CN10") (pin "31") (pinfunction "31_31") (pintype "passive"))
      (node (ref "SB182") (pin "2") (pinfunction "2_2") (pintype "passive"))
    )
    (net (code "148") (name "Net-(CN10-Pad32)") (class "Default")
      (node (ref "CN10") (pin "32") (pinfunction "32_32") (pintype "passive"))
      (node (ref "SB188") (pin "1") (pinfunction "1_1") (pintype "passive"))
    )
    (net (code "149") (name "Net-(CN11-Pad25)") (class "Default")
      (node (ref "CN11") (pin "25") (pinfunction "25_25") (pintype "passive"))
      (node (ref "SB145") (pin "2") (pinfunction "2_2") (pintype "passive"))
    )
    (net (code "150") (name "Net-(CN11-Pad27)") (class "Default")
      (node (ref "CN11") (pin "27") (pinfunction "27_27") (pintype "passive"))
      (node (ref "SB146") (pin "2") (pinfunction "2_2") (pintype "passive"))
    )
    (net (code "151") (name "Net-(CN11-Pad29)") (class "Default")
      (node (ref "CN11") (pin "29") (pinfunction "29_29") (pintype "passive"))
      (node (ref "SB147") (pin "2") (pinfunction "2_2") (pintype "passive"))
    )
    (net (code "152") (name "Net-(CN11-Pad31)") (class "Default")
      (node (ref "CN11") (pin "31") (pinfunction "31_31") (pintype "passive"))
      (node (ref "SB156") (pin "2") (pinfunction "2_2") (pintype "passive"))
    )
    (net (code "153") (name "Net-(CN11-Pad34)") (class "Default")
      (node (ref "CN11") (pin "34") (pinfunction "34_34") (pintype "passive"))
      (node (ref "SB144") (pin "1") (pinfunction "1_1") (pintype "passive"))
    )
    (net (code "154") (name "Net-(CN11-Pad65)") (class "Default")
      (node (ref "CN11") (pin "65") (pinfunction "65_65") (pintype "passive"))
      (node (ref "SB191") (pin "2") (pinfunction "2_2") (pintype "passive"))
    )
    (net (code "155") (name "Net-(CN11-Pad66)") (class "Default")
      (node (ref "CN11") (pin "66") (pinfunction "66_66") (pintype "passive"))
      (node (ref "SB192") (pin "1") (pinfunction "1_1") (pintype "passive"))
    )
    (net (code "156") (name "Net-(CN11-Pad68)") (class "Default")
      (node (ref "CN11") (pin "68") (pinfunction "68_68") (pintype "passive"))
      (node (ref "SB194") (pin "1") (pinfunction "1_1") (pintype "passive"))
    )
    (net (code "157") (name "Net-(CN11-Pad70)") (class "Default")
      (node (ref "CN11") (pin "70") (pinfunction "70_70") (pintype "passive"))
      (node (ref "SB196") (pin "1") (pinfunction "1_1") (pintype "passive"))
    )
    (net (code "158") (name "Net-(CN12-Pad1)") (class "Default")
      (node (ref "CN12") (pin "1") (pinfunction "1_1") (pintype "passive"))
      (node (ref "SB136") (pin "2") (pinfunction "2_2") (pintype "passive"))
    )
    (net (code "159") (name "Net-(CN12-Pad2)") (class "Default")
      (node (ref "CN12") (pin "2") (pinfunction "2_2") (pintype "passive"))
      (node (ref "SB137") (pin "2") (pinfunction "2_2") (pintype "passive"))
    )
    (net (code "160") (name "Net-(CN12-Pad7)") (class "Default")
      (node (ref "CN12") (pin "7") (pinfunction "7_7") (pintype "passive"))
      (node (ref "CN7") (pin "6") (pinfunction "6_6") (pintype "passive"))
      (node (ref "SB119") (pin "2") (pinfunction "2_2") (pintype "passive"))
    )
    (net (code "161") (name "Net-(CN12-Pad66)") (class "Default")
      (node (ref "CN12") (pin "66") (pinfunction "66_66") (pintype "passive"))
      (node (ref "SB193") (pin "1") (pinfunction "1_1") (pintype "passive"))
    )
    (net (code "162") (name "Net-(CN12-Pad67)") (class "Default")
      (node (ref "CN12") (pin "67") (pinfunction "67_67") (pintype "passive"))
      (node (ref "SB195") (pin "2") (pinfunction "2_2") (pintype "passive"))
    )
    (net (code "163") (name "Net-(LD1-A)") (class "Default")
      (node (ref "LD1") (pin "1") (pinfunction "A_1") (pintype "passive"))
      (node (ref "R31") (pin "2") (pinfunction "2_2") (pintype "passive"))
    )
    (net (code "164") (name "Net-(R37-Pad2)") (class "Default")
      (node (ref "R37") (pin "2") (pinfunction "2_2") (pintype "passive"))
      (node (ref "SB123") (pin "1") (pinfunction "1_1") (pintype "passive"))
      (node (ref "SB124") (pin "2") (pinfunction "2_2") (pintype "passive"))
    )
    (net (code "165") (name "Net-(U8-IN+)") (class "Default")
      (node (ref "R36") (pin "1") (pinfunction "1_1") (pintype "passive"))
      (node (ref "R37") (pin "1") (pinfunction "1_1") (pintype "passive"))
      (node (ref "U8") (pin "1") (pinfunction "IN+_1") (pintype "input"))
    )
    (net (code "166") (name "Net-(U8-IN-)") (class "Default")
      (node (ref "R31") (pin "1") (pinfunction "1_1") (pintype "passive"))
      (node (ref "U8") (pin "3") (pinfunction "IN-_3") (pintype "input"))
      (node (ref "U8") (pin "4") (pinfunction "OUT_4") (pintype "output"))
    )
    (net (code "167") (name "U5V") (class "Default")
      (node (ref "CN12") (pin "8") (pinfunction "8_8") (pintype "passive"))
    )
    (net (code "168") (name "VBAT") (class "Default")
      (node (ref "CN11") (pin "33") (pinfunction "33_33") (pintype "passive"))
    )
    (net (code "169") (name "VDD") (class "Default")
      (node (ref "CN11") (pin "5") (pinfunction "5_5") (pintype "passive"))
    )
    (net (code "170") (name "VDD_MCU") (class "Default")
      (node (ref "SB112") (pin "1") (pinfunction "1_1") (pintype "passive"))
    )
    (net (code "171") (name "VIN") (class "Default")
      (node (ref "CN11") (pin "24") (pinfunction "24_24") (pintype "passive"))
      (node (ref "CN8") (pin "15") (pinfunction "15_15") (pintype "passive"))
    )
    (net (code "172") (name "VREF+") (class "Default")
      (node (ref "C45") (pin "1") (pinfunction "1_1") (pintype "passive"))
      (node (ref "SB119") (pin "1") (pinfunction "1_1") (pintype "passive"))
    )
    (net (code "173") (name "unconnected-(CN8-Pad1)") (class "Default")
      (node (ref "CN8") (pin "1") (pinfunction "1_1") (pintype "passive"))
    )
    (net (code "174") (name "unconnected-(CN11-Pad10)") (class "Default")
      (node (ref "CN11") (pin "10") (pinfunction "10_10") (pintype "passive"))
    )
    (net (code "175") (name "unconnected-(CN11-Pad26)") (class "Default")
      (node (ref "CN11") (pin "26") (pinfunction "26_26") (pintype "passive"))
    )
    (net (code "176") (name "unconnected-(CN11-Pad67)") (class "Default")
      (node (ref "CN11") (pin "67") (pinfunction "67_67") (pintype "passive"))
    )
  )
)
